# actuator.net
KiCad netlist of a schematic drawn in Altium Designer
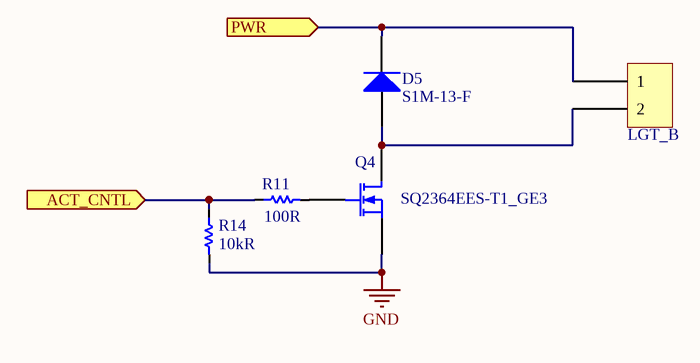
[diagram p0: actuator.SchDoc]

(export (version "E")
  (design (tool "Eeschema 10.0.6"))
  (components
    (comp (ref "D5")
      (value "S1M-13-F")
      (footprint "SMA")
      (description "Default Diode")
      (libsource (lib "Miscellaneous Devices") (part "Diode"))
    )
    (comp (ref "LGT_B")
      (value "MOLEX_43650_2")
      (footprint "MOLEX_43650_2")
      (fields (field (name "MANUFACTURER") "Molex") (field (name "MANUFACTURER PART NUMBER") "43650-0227"))
      (libsource (lib "food_box") (part "MOLEX_43650_2"))
    )
    (comp (ref "Q4")
      (value "MOSFET-N")
      (footprint "SOT23-3")
      (description "Trans MOSFET N-CH 60V 2A Automotive 3-Pin SOT-23 T/R")
      (fields
        (field (name "MANUFACTURER") "Vishay")
        (field (name "MANUFACTURER PART NUMBER") "SQ2364EES-T1_GE3")
      )
      (libsource (lib "Miscellaneous Devices") (part "MOSFET-N"))
    )
    (comp (ref "R11")
      (value "value")
      (footprint "RES 0603 L")
      (description "CRGCQ 0603 100R 5%")
      (fields
        (field (name "MANUFACTURER") "TE Connectivity")
        (field (name "MANUFACTURER PART NUMBER") "CRGCQ0603J100R")
        (field (name "RESISTANCE") "100R")
      )
      (libsource (lib "streetbot") (part "RES 0603"))
    )
    (comp (ref "R14")
      (value "value")
      (footprint "RES 0603 L")
      (description "TE CONNECTIVITY - CRGCQ0603J10K - RES, 10K, 5%, 0603, THICK FILM")
      (fields
        (field (name "MANUFACTURER") "TE Connectivity")
        (field (name "MANUFACTURER PART NUMBER") "CRGCQ0603J10K")
        (field (name "RESISTANCE") "10kR")
      )
      (libsource (lib "streetbot") (part "RES 0603"))
    )
  )
  (nets
    (net (code "1") (name "/ACT_CNTL") (class "Default")
      (node (ref "R11") (pin "2") (pinfunction "2_2") (pintype "passive"))
      (node (ref "R14") (pin "2") (pinfunction "2_2") (pintype "passive"))
    )
    (net (code "2") (name "/PWR") (class "Default")
      (node (ref "D5") (pin "2") (pinfunction "K_2") (pintype "passive"))
      (node (ref "LGT_B") (pin "1") (pinfunction "1_1") (pintype "passive"))
    )
    (net (code "3") (name "GND") (class "Default")
      (node (ref "Q4") (pin "3") (pinfunction "S_3") (pintype "passive"))
      (node (ref "R14") (pin "1") (pinfunction "1_1") (pintype "passive"))
    )
    (net (code "4") (name "Net-(D5-A)") (class "Default")
      (node (ref "D5") (pin "1") (pinfunction "A_1") (pintype "passive"))
      (node (ref "LGT_B") (pin "2") (pinfunction "2_2") (pintype "passive"))
      (node (ref "Q4") (pin "1") (pinfunction "D_1") (pintype "passive"))
    )
    (net (code "5") (name "Net-(Q4-G)") (class "Default")
      (node (ref "Q4") (pin "2") (pinfunction "G_2") (pintype "passive"))
      (node (ref "R11") (pin "1") (pinfunction "1_1") (pintype "passive"))
    )
  )
)
